# Group_8.net
KiCad netlist of a schematic drawn in EAGLE
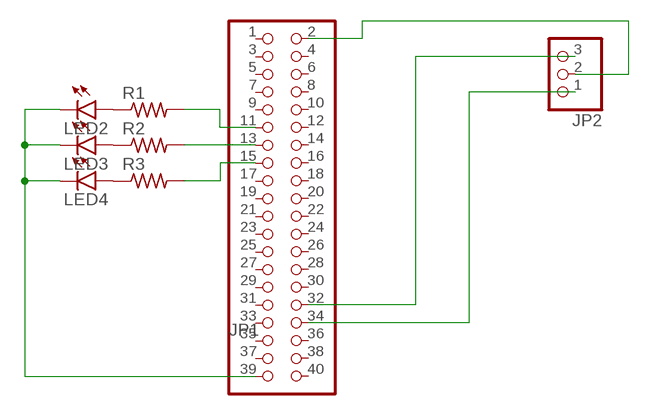
[diagram p0: schematic, sheet 1]

(export (version "E")
  (design (tool "Eeschema 10.0.6"))
  (components
    (comp (ref "JP1")
      (value "PINHD-2X20")
      (footprint "eagle-import:2X20")
      (libsource (lib "eagle-import") (part "PINHD-2X20"))
    )
    (comp (ref "JP2")
      (value "PINHD-1X3")
      (footprint "eagle-import:1X03")
      (libsource (lib "eagle-import") (part "PINHD-1X3"))
    )
    (comp (ref "LED2")
      (value "LED5MM")
      (footprint "eagle-import:LED5MM")
      (libsource (lib "eagle-import") (part "LED5MM"))
    )
    (comp (ref "LED3")
      (value "LED5MM")
      (footprint "eagle-import:LED5MM")
      (libsource (lib "eagle-import") (part "LED5MM"))
    )
    (comp (ref "LED4")
      (value "LED5MM")
      (footprint "eagle-import:LED5MM")
      (libsource (lib "eagle-import") (part "LED5MM"))
    )
    (comp (ref "R1")
      (value "R-US_0204/7")
      (footprint "eagle-import:0204_7")
      (libsource (lib "eagle-import") (part "R-US_0204/7"))
    )
    (comp (ref "R2")
      (value "R-US_0204/7")
      (footprint "eagle-import:0204_7")
      (libsource (lib "eagle-import") (part "R-US_0204/7"))
    )
    (comp (ref "R3")
      (value "R-US_0204/7")
      (footprint "eagle-import:0204_7")
      (libsource (lib "eagle-import") (part "R-US_0204/7"))
    )
  )
  (nets
    (net (code "1") (name "Net-(JP1-Pad2)") (class "Default")
      (node (ref "JP1") (pin "2") (pinfunction "2_2") (pintype "passive"))
      (node (ref "JP2") (pin "2") (pinfunction "2_2") (pintype "passive"))
    )
    (net (code "2") (name "Net-(JP1-Pad11)") (class "Default")
      (node (ref "JP1") (pin "11") (pinfunction "11_11") (pintype "passive"))
      (node (ref "R1") (pin "2") (pinfunction "2_2") (pintype "passive"))
    )
    (net (code "3") (name "Net-(JP1-Pad13)") (class "Default")
      (node (ref "JP1") (pin "13") (pinfunction "13_13") (pintype "passive"))
      (node (ref "R2") (pin "2") (pinfunction "2_2") (pintype "passive"))
    )
    (net (code "4") (name "Net-(JP1-Pad15)") (class "Default")
      (node (ref "JP1") (pin "15") (pinfunction "15_15") (pintype "passive"))
      (node (ref "R3") (pin "2") (pinfunction "2_2") (pintype "passive"))
    )
    (net (code "5") (name "Net-(JP1-Pad32)") (class "Default")
      (node (ref "JP1") (pin "32") (pinfunction "32_32") (pintype "passive"))
      (node (ref "JP2") (pin "3") (pinfunction "3_3") (pintype "passive"))
    )
    (net (code "6") (name "Net-(JP1-Pad34)") (class "Default")
      (node (ref "JP1") (pin "34") (pinfunction "34_34") (pintype "passive"))
      (node (ref "JP2") (pin "1") (pinfunction "1_1") (pintype "passive"))
    )
    (net (code "7") (name "Net-(LED2-C)") (class "Default")
      (node (ref "JP1") (pin "39") (pinfunction "39_39") (pintype "passive"))
      (node (ref "LED2") (pin "K") (pinfunction "C_K") (pintype "passive"))
      (node (ref "LED3") (pin "K") (pinfunction "C_K") (pintype "passive"))
      (node (ref "LED4") (pin "K") (pinfunction "C_K") (pintype "passive"))
    )
    (net (code "8") (name "Net-(LED2-PadA)") (class "Default")
      (node (ref "LED2") (pin "A") (pinfunction "A_A") (pintype "passive"))
      (node (ref "R1") (pin "1") (pinfunction "1_1") (pintype "passive"))
    )
    (net (code "9") (name "Net-(LED3-PadA)") (class "Default")
      (node (ref "LED3") (pin "A") (pinfunction "A_A") (pintype "passive"))
      (node (ref "R2") (pin "1") (pinfunction "1_1") (pintype "passive"))
    )
    (net (code "10") (name "Net-(LED4-PadA)") (class "Default")
      (node (ref "LED4") (pin "A") (pinfunction "A_A") (pintype "passive"))
      (node (ref "R3") (pin "1") (pinfunction "1_1") (pintype "passive"))
    )
    (net (code "11") (name "unconnected-(JP1-Pad1)") (class "Default")
      (node (ref "JP1") (pin "1") (pinfunction "1_1") (pintype "passive"))
    )
    (net (code "12") (name "unconnected-(JP1-Pad3)") (class "Default")
      (node (ref "JP1") (pin "3") (pinfunction "3_3") (pintype "passive"))
    )
    (net (code "13") (name "unconnected-(JP1-Pad4)") (class "Default")
      (node (ref "JP1") (pin "4") (pinfunction "4_4") (pintype "passive"))
    )
    (net (code "14") (name "unconnected-(JP1-Pad5)") (class "Default")
      (node (ref "JP1") (pin "5") (pinfunction "5_5") (pintype "passive"))
    )
    (net (code "15") (name "unconnected-(JP1-Pad6)") (class "Default")
      (node (ref "JP1") (pin "6") (pinfunction "6_6") (pintype "passive"))
    )
    (net (code "16") (name "unconnected-(JP1-Pad7)") (class "Default")
      (node (ref "JP1") (pin "7") (pinfunction "7_7") (pintype "passive"))
    )
    (net (code "17") (name "unconnected-(JP1-Pad8)") (class "Default")
      (node (ref "JP1") (pin "8") (pinfunction "8_8") (pintype "passive"))
    )
    (net (code "18") (name "unconnected-(JP1-Pad9)") (class "Default")
      (node (ref "JP1") (pin "9") (pinfunction "9_9") (pintype "passive"))
    )
    (net (code "19") (name "unconnected-(JP1-Pad10)") (class "Default")
      (node (ref "JP1") (pin "10") (pinfunction "10_10") (pintype "passive"))
    )
    (net (code "20") (name "unconnected-(JP1-Pad12)") (class "Default")
      (node (ref "JP1") (pin "12") (pinfunction "12_12") (pintype "passive"))
    )
    (net (code "21") (name "unconnected-(JP1-Pad14)") (class "Default")
      (node (ref "JP1") (pin "14") (pinfunction "14_14") (pintype "passive"))
    )
    (net (code "22") (name "unconnected-(JP1-Pad16)") (class "Default")
      (node (ref "JP1") (pin "16") (pinfunction "16_16") (pintype "passive"))
    )
    (net (code "23") (name "unconnected-(JP1-Pad17)") (class "Default")
      (node (ref "JP1") (pin "17") (pinfunction "17_17") (pintype "passive"))
    )
    (net (code "24") (name "unconnected-(JP1-Pad18)") (class "Default")
      (node (ref "JP1") (pin "18") (pinfunction "18_18") (pintype "passive"))
    )
    (net (code "25") (name "unconnected-(JP1-Pad19)") (class "Default")
      (node (ref "JP1") (pin "19") (pinfunction "19_19") (pintype "passive"))
    )
    (net (code "26") (name "unconnected-(JP1-Pad20)") (class "Default")
      (node (ref "JP1") (pin "20") (pinfunction "20_20") (pintype "passive"))
    )
    (net (code "27") (name "unconnected-(JP1-Pad21)") (class "Default")
      (node (ref "JP1") (pin "21") (pinfunction "21_21") (pintype "passive"))
    )
    (net (code "28") (name "unconnected-(JP1-Pad22)") (class "Default")
      (node (ref "JP1") (pin "22") (pinfunction "22_22") (pintype "passive"))
    )
    (net (code "29") (name "unconnected-(JP1-Pad23)") (class "Default")
      (node (ref "JP1") (pin "23") (pinfunction "23_23") (pintype "passive"))
    )
    (net (code "30") (name "unconnected-(JP1-Pad24)") (class "Default")
      (node (ref "JP1") (pin "24") (pinfunction "24_24") (pintype "passive"))
    )
    (net (code "31") (name "unconnected-(JP1-Pad25)") (class "Default")
      (node (ref "JP1") (pin "25") (pinfunction "25_25") (pintype "passive"))
    )
    (net (code "32") (name "unconnected-(JP1-Pad26)") (class "Default")
      (node (ref "JP1") (pin "26") (pinfunction "26_26") (pintype "passive"))
    )
    (net (code "33") (name "unconnected-(JP1-Pad27)") (class "Default")
      (node (ref "JP1") (pin "27") (pinfunction "27_27") (pintype "passive"))
    )
    (net (code "34") (name "unconnected-(JP1-Pad28)") (class "Default")
      (node (ref "JP1") (pin "28") (pinfunction "28_28") (pintype "passive"))
    )
    (net (code "35") (name "unconnected-(JP1-Pad29)") (class "Default")
      (node (ref "JP1") (pin "29") (pinfunction "29_29") (pintype "passive"))
    )
    (net (code "36") (name "unconnected-(JP1-Pad30)") (class "Default")
      (node (ref "JP1") (pin "30") (pinfunction "30_30") (pintype "passive"))
    )
    (net (code "37") (name "unconnected-(JP1-Pad31)") (class "Default")
      (node (ref "JP1") (pin "31") (pinfunction "31_31") (pintype "passive"))
    )
    (net (code "38") (name "unconnected-(JP1-Pad33)") (class "Default")
      (node (ref "JP1") (pin "33") (pinfunction "33_33") (pintype "passive"))
    )
    (net (code "39") (name "unconnected-(JP1-Pad35)") (class "Default")
      (node (ref "JP1") (pin "35") (pinfunction "35_35") (pintype "passive"))
    )
    (net (code "40") (name "unconnected-(JP1-Pad36)") (class "Default")
      (node (ref "JP1") (pin "36") (pinfunction "36_36") (pintype "passive"))
    )
    (net (code "41") (name "unconnected-(JP1-Pad37)") (class "Default")
      (node (ref "JP1") (pin "37") (pinfunction "37_37") (pintype "passive"))
    )
    (net (code "42") (name "unconnected-(JP1-Pad38)") (class "Default")
      (node (ref "JP1") (pin "38") (pinfunction "38_38") (pintype "passive"))
    )
    (net (code "43") (name "unconnected-(JP1-Pad40)") (class "Default")
      (node (ref "JP1") (pin "40") (pinfunction "40_40") (pintype "passive"))
    )
  )
)
